# Slot_Detectors.net
KiCad netlist of a schematic drawn in Altium Designer
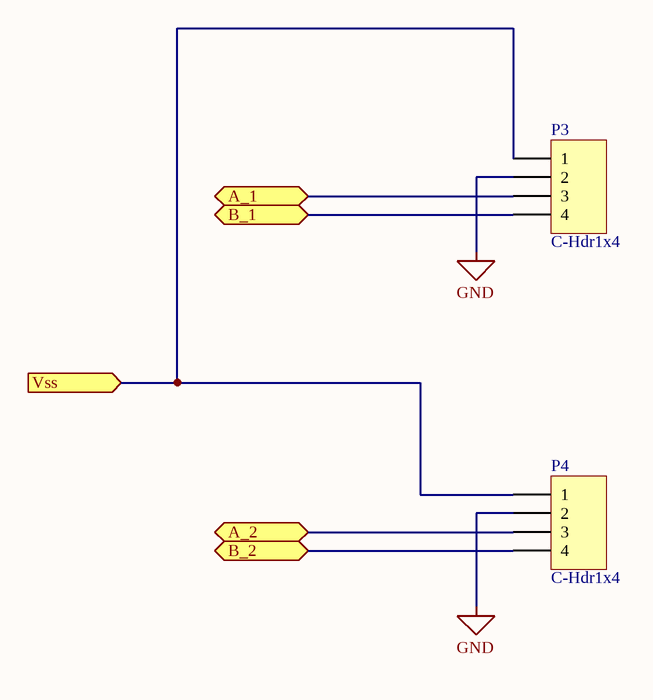
[diagram p0: Slot_Detectors.SchDoc]

(export (version "E")
  (design (tool "Eeschema 10.0.6"))
  (components
    (comp (ref "P3")
      (value "C-Hdr1x4")
      (footprint "HDR1X4_LGE1.0")
      (description "Header, 4-Pin")
      (fields (field (name "PUBLISHER") "Altium Limited"))
      (libsource (lib "PartsDatabaseV16.1") (part "C-Hdr1x4"))
    )
    (comp (ref "P4")
      (value "C-Hdr1x4")
      (footprint "HDR1X4_LGE1.0")
      (description "Header, 4-Pin")
      (fields (field (name "PUBLISHER") "Altium Limited"))
      (libsource (lib "PartsDatabaseV16.1") (part "C-Hdr1x4"))
    )
  )
  (nets
    (net (code "1") (name "/A_1") (class "Default")
      (node (ref "P3") (pin "3") (pinfunction "3_3") (pintype "passive"))
    )
    (net (code "2") (name "/A_2") (class "Default")
      (node (ref "P4") (pin "3") (pinfunction "3_3") (pintype "passive"))
    )
    (net (code "3") (name "/B_1") (class "Default")
      (node (ref "P3") (pin "4") (pinfunction "4_4") (pintype "passive"))
    )
    (net (code "4") (name "/B_2") (class "Default")
      (node (ref "P4") (pin "4") (pinfunction "4_4") (pintype "passive"))
    )
    (net (code "5") (name "/Vss") (class "Default")
      (node (ref "P3") (pin "1") (pinfunction "1_1") (pintype "passive"))
      (node (ref "P4") (pin "1") (pinfunction "1_1") (pintype "passive"))
    )
    (net (code "6") (name "GND") (class "Default")
      (node (ref "P3") (pin "2") (pinfunction "2_2") (pintype "passive"))
      (node (ref "P4") (pin "2") (pinfunction "2_2") (pintype "passive"))
    )
  )
)
